# CPM_Uext.net
KiCad netlist of a schematic drawn in EAGLE
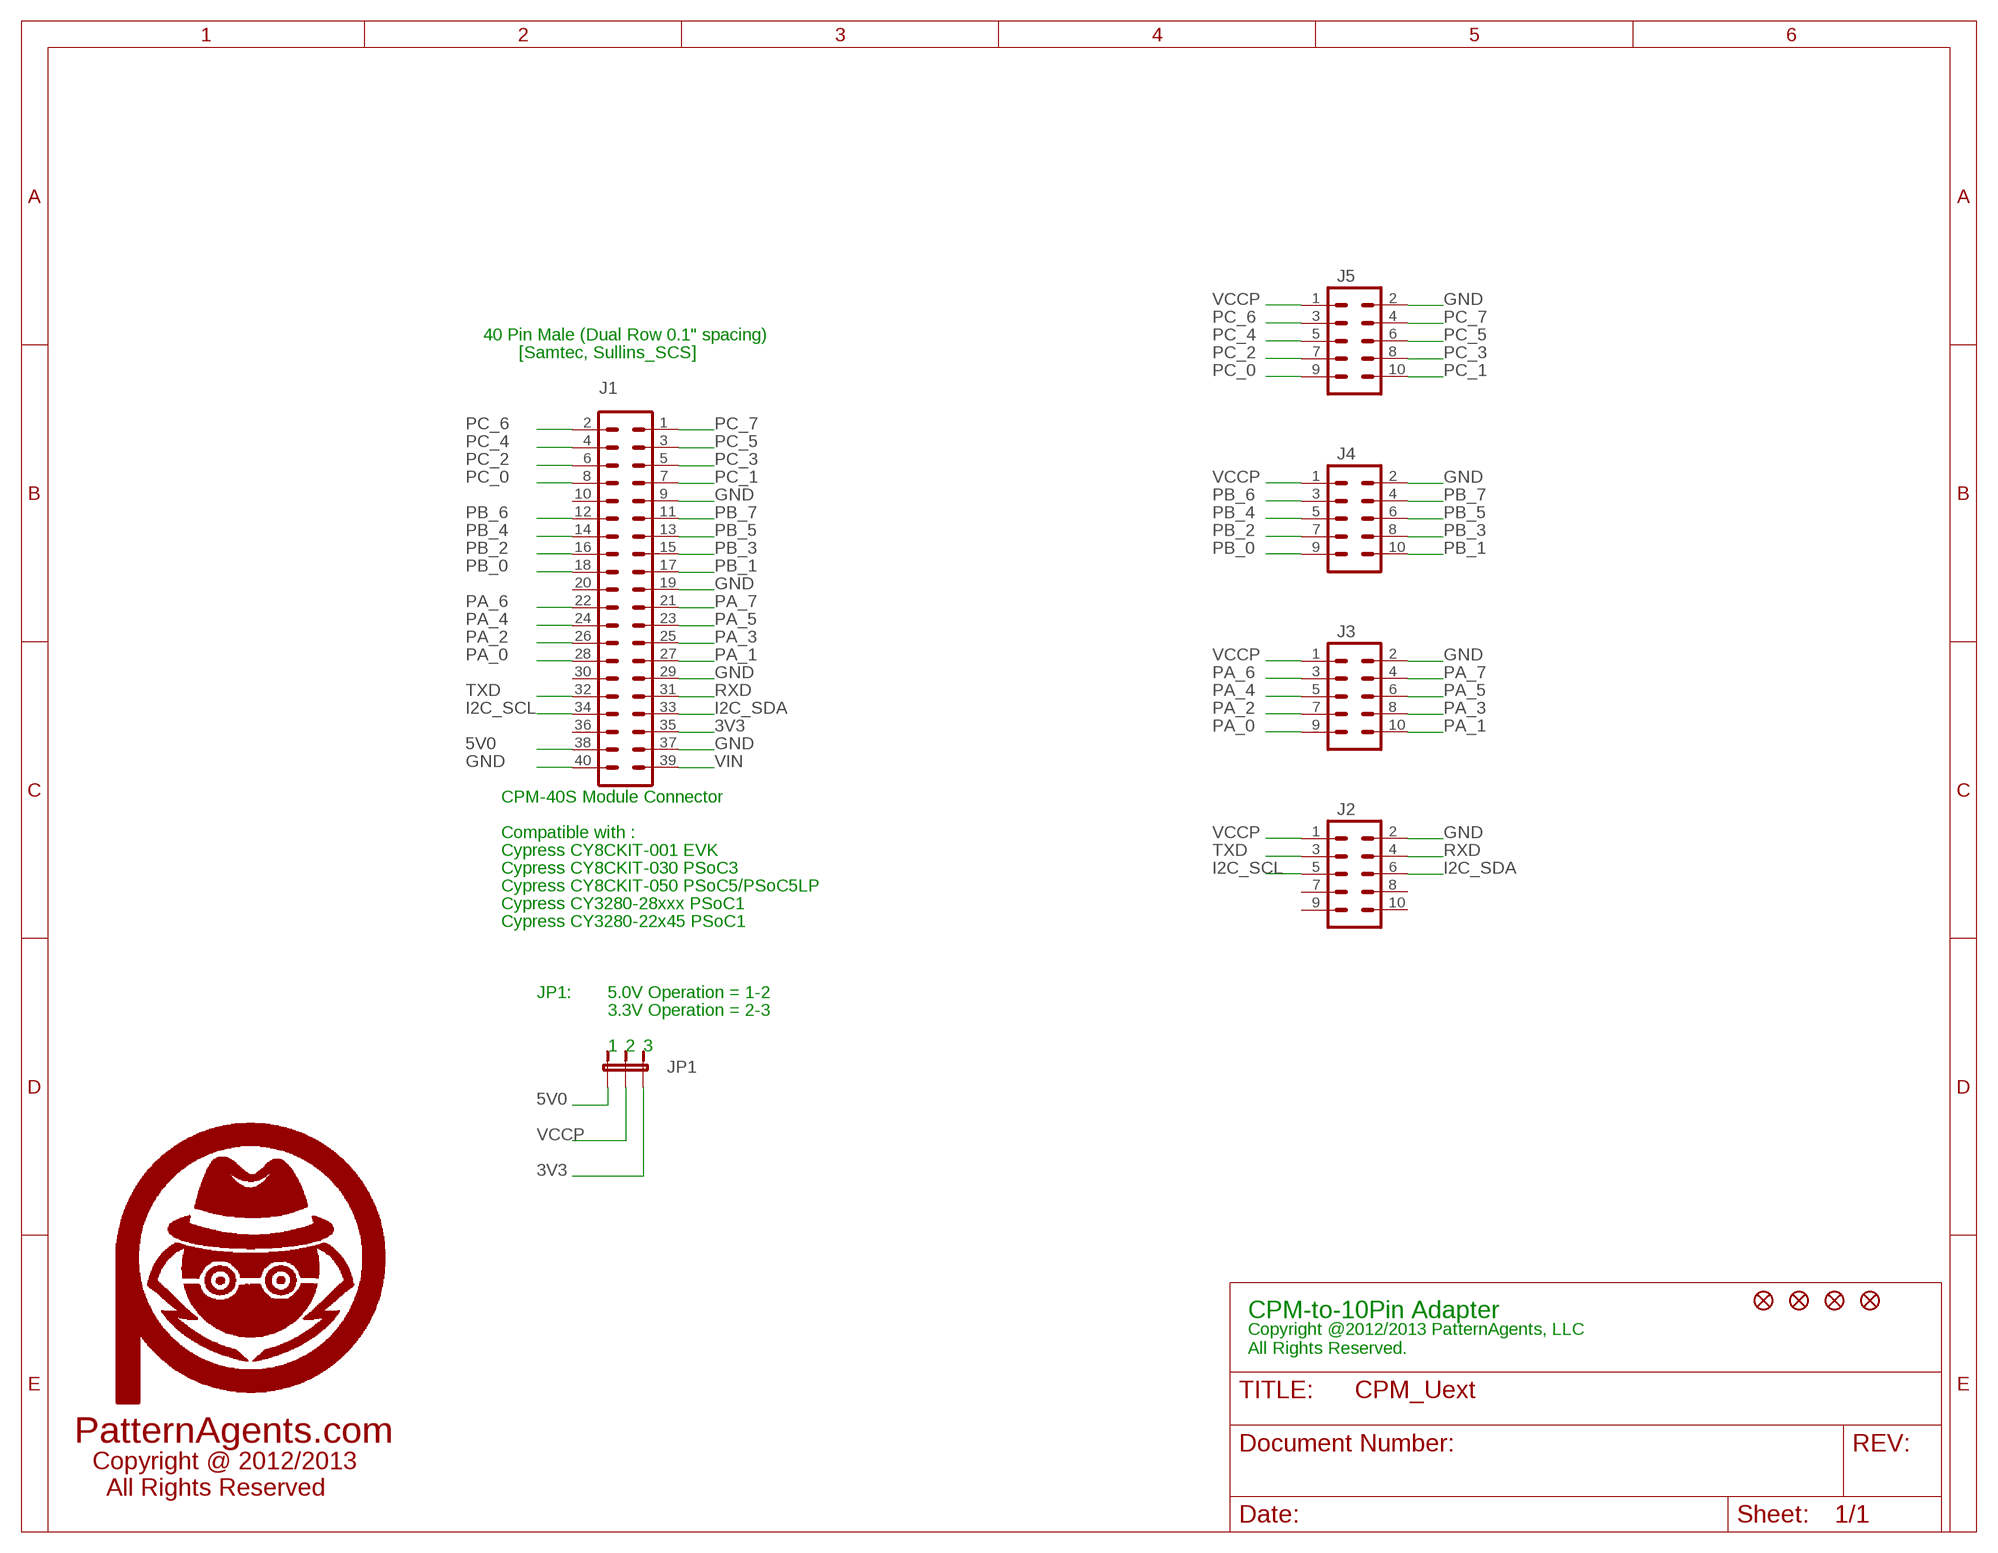
[diagram p0: schematic, sheet 1]

(export (version "E")
  (design (tool "Eeschema 10.0.6"))
  (components
    (comp (ref "J1")
      (value "SULLINS_SCS")
      (footprint "eagle-import:MA20-2")
      (fields (field (name "MF") "Sullins") (field (name "MPN") "PBC20DBAN"))
      (libsource (lib "eagle-import") (part "MA20-2"))
    )
    (comp (ref "J2")
      (value "M05X2")
      (footprint "eagle-import:2X5-UEXT")
      (libsource (lib "eagle-import") (part "M05X2"))
    )
    (comp (ref "J3")
      (value "M05X2")
      (footprint "eagle-import:2X5-UEXT")
      (libsource (lib "eagle-import") (part "M05X2"))
    )
    (comp (ref "J4")
      (value "M05X2")
      (footprint "eagle-import:2X5-UEXT")
      (libsource (lib "eagle-import") (part "M05X2"))
    )
    (comp (ref "J5")
      (value "M05X2")
      (footprint "eagle-import:2X5-UEXT")
      (libsource (lib "eagle-import") (part "M05X2"))
    )
    (comp (ref "JP1")
      (value "JUMPER-3PTH")
      (footprint "eagle-import:1X03")
      (libsource (lib "eagle-import") (part "JUMPER-3PTH"))
    )
    (comp (ref "JP2")
      (value "FIDUCIAL1.5X3")
      (footprint "eagle-import:FIDUCIAL-1.5X3")
      (libsource (lib "eagle-import") (part "FIDUCIAL1.5X3"))
    )
    (comp (ref "JP3")
      (value "FIDUCIAL1.5X3")
      (footprint "eagle-import:FIDUCIAL-1.5X3")
      (libsource (lib "eagle-import") (part "FIDUCIAL1.5X3"))
    )
    (comp (ref "JP4")
      (value "FIDUCIAL1.5X3")
      (footprint "eagle-import:FIDUCIAL-1.5X3")
      (libsource (lib "eagle-import") (part "FIDUCIAL1.5X3"))
    )
    (comp (ref "JP5")
      (value "FIDUCIAL1.5X3")
      (footprint "eagle-import:FIDUCIAL-1.5X3")
      (libsource (lib "eagle-import") (part "FIDUCIAL1.5X3"))
    )
    (comp (ref "U$1")
      (value "LOGO_PA_AGENTLARGE")
      (footprint "eagle-import:LOGO_PA_AGENT_LARGE")
      (libsource (lib "eagle-import") (part "LOGO_PA_AGENTLARGE"))
    )
  )
  (nets
    (net (code "1") (name "/3V3") (class "Default")
      (node (ref "J1") (pin "35") (pinfunction "35_35") (pintype "passive"))
      (node (ref "JP1") (pin "3") (pinfunction "3_3") (pintype "passive"))
    )
    (net (code "2") (name "/5V0") (class "Default")
      (node (ref "J1") (pin "38") (pinfunction "38_38") (pintype "passive"))
      (node (ref "JP1") (pin "1") (pinfunction "1_1") (pintype "passive"))
    )
    (net (code "3") (name "/GND") (class "Default")
      (node (ref "J1") (pin "19") (pinfunction "19_19") (pintype "passive"))
      (node (ref "J1") (pin "29") (pinfunction "29_29") (pintype "passive"))
      (node (ref "J1") (pin "37") (pinfunction "37_37") (pintype "passive"))
      (node (ref "J1") (pin "40") (pinfunction "40_40") (pintype "passive"))
      (node (ref "J1") (pin "9") (pinfunction "9_9") (pintype "passive"))
      (node (ref "J2") (pin "2") (pinfunction "2_2") (pintype "passive"))
      (node (ref "J3") (pin "2") (pinfunction "2_2") (pintype "passive"))
      (node (ref "J4") (pin "2") (pinfunction "2_2") (pintype "passive"))
      (node (ref "J5") (pin "2") (pinfunction "2_2") (pintype "passive"))
    )
    (net (code "4") (name "/I2C_SCL") (class "Default")
      (node (ref "J1") (pin "34") (pinfunction "34_34") (pintype "passive"))
      (node (ref "J2") (pin "5") (pinfunction "5_5") (pintype "passive"))
    )
    (net (code "5") (name "/I2C_SDA") (class "Default")
      (node (ref "J1") (pin "33") (pinfunction "33_33") (pintype "passive"))
      (node (ref "J2") (pin "6") (pinfunction "6_6") (pintype "passive"))
    )
    (net (code "6") (name "/PA_0") (class "Default")
      (node (ref "J1") (pin "28") (pinfunction "28_28") (pintype "passive"))
      (node (ref "J3") (pin "9") (pinfunction "9_9") (pintype "passive"))
    )
    (net (code "7") (name "/PA_1") (class "Default")
      (node (ref "J1") (pin "27") (pinfunction "27_27") (pintype "passive"))
      (node (ref "J3") (pin "10") (pinfunction "10_10") (pintype "passive"))
    )
    (net (code "8") (name "/PA_2") (class "Default")
      (node (ref "J1") (pin "26") (pinfunction "26_26") (pintype "passive"))
      (node (ref "J3") (pin "7") (pinfunction "7_7") (pintype "passive"))
    )
    (net (code "9") (name "/PA_3") (class "Default")
      (node (ref "J1") (pin "25") (pinfunction "25_25") (pintype "passive"))
      (node (ref "J3") (pin "8") (pinfunction "8_8") (pintype "passive"))
    )
    (net (code "10") (name "/PA_4") (class "Default")
      (node (ref "J1") (pin "24") (pinfunction "24_24") (pintype "passive"))
      (node (ref "J3") (pin "5") (pinfunction "5_5") (pintype "passive"))
    )
    (net (code "11") (name "/PA_5") (class "Default")
      (node (ref "J1") (pin "23") (pinfunction "23_23") (pintype "passive"))
      (node (ref "J3") (pin "6") (pinfunction "6_6") (pintype "passive"))
    )
    (net (code "12") (name "/PA_6") (class "Default")
      (node (ref "J1") (pin "22") (pinfunction "22_22") (pintype "passive"))
      (node (ref "J3") (pin "3") (pinfunction "3_3") (pintype "passive"))
    )
    (net (code "13") (name "/PA_7") (class "Default")
      (node (ref "J1") (pin "21") (pinfunction "21_21") (pintype "passive"))
      (node (ref "J3") (pin "4") (pinfunction "4_4") (pintype "passive"))
    )
    (net (code "14") (name "/PB_0") (class "Default")
      (node (ref "J1") (pin "18") (pinfunction "18_18") (pintype "passive"))
      (node (ref "J4") (pin "9") (pinfunction "9_9") (pintype "passive"))
    )
    (net (code "15") (name "/PB_1") (class "Default")
      (node (ref "J1") (pin "17") (pinfunction "17_17") (pintype "passive"))
      (node (ref "J4") (pin "10") (pinfunction "10_10") (pintype "passive"))
    )
    (net (code "16") (name "/PB_2") (class "Default")
      (node (ref "J1") (pin "16") (pinfunction "16_16") (pintype "passive"))
      (node (ref "J4") (pin "7") (pinfunction "7_7") (pintype "passive"))
    )
    (net (code "17") (name "/PB_3") (class "Default")
      (node (ref "J1") (pin "15") (pinfunction "15_15") (pintype "passive"))
      (node (ref "J4") (pin "8") (pinfunction "8_8") (pintype "passive"))
    )
    (net (code "18") (name "/PB_4") (class "Default")
      (node (ref "J1") (pin "14") (pinfunction "14_14") (pintype "passive"))
      (node (ref "J4") (pin "5") (pinfunction "5_5") (pintype "passive"))
    )
    (net (code "19") (name "/PB_5") (class "Default")
      (node (ref "J1") (pin "13") (pinfunction "13_13") (pintype "passive"))
      (node (ref "J4") (pin "6") (pinfunction "6_6") (pintype "passive"))
    )
    (net (code "20") (name "/PB_6") (class "Default")
      (node (ref "J1") (pin "12") (pinfunction "12_12") (pintype "passive"))
      (node (ref "J4") (pin "3") (pinfunction "3_3") (pintype "passive"))
    )
    (net (code "21") (name "/PB_7") (class "Default")
      (node (ref "J1") (pin "11") (pinfunction "11_11") (pintype "passive"))
      (node (ref "J4") (pin "4") (pinfunction "4_4") (pintype "passive"))
    )
    (net (code "22") (name "/PC_0") (class "Default")
      (node (ref "J1") (pin "8") (pinfunction "8_8") (pintype "passive"))
      (node (ref "J5") (pin "9") (pinfunction "9_9") (pintype "passive"))
    )
    (net (code "23") (name "/PC_1") (class "Default")
      (node (ref "J1") (pin "7") (pinfunction "7_7") (pintype "passive"))
      (node (ref "J5") (pin "10") (pinfunction "10_10") (pintype "passive"))
    )
    (net (code "24") (name "/PC_2") (class "Default")
      (node (ref "J1") (pin "6") (pinfunction "6_6") (pintype "passive"))
      (node (ref "J5") (pin "7") (pinfunction "7_7") (pintype "passive"))
    )
    (net (code "25") (name "/PC_3") (class "Default")
      (node (ref "J1") (pin "5") (pinfunction "5_5") (pintype "passive"))
      (node (ref "J5") (pin "8") (pinfunction "8_8") (pintype "passive"))
    )
    (net (code "26") (name "/PC_4") (class "Default")
      (node (ref "J1") (pin "4") (pinfunction "4_4") (pintype "passive"))
      (node (ref "J5") (pin "5") (pinfunction "5_5") (pintype "passive"))
    )
    (net (code "27") (name "/PC_5") (class "Default")
      (node (ref "J1") (pin "3") (pinfunction "3_3") (pintype "passive"))
      (node (ref "J5") (pin "6") (pinfunction "6_6") (pintype "passive"))
    )
    (net (code "28") (name "/PC_6") (class "Default")
      (node (ref "J1") (pin "2") (pinfunction "2_2") (pintype "passive"))
      (node (ref "J5") (pin "3") (pinfunction "3_3") (pintype "passive"))
    )
    (net (code "29") (name "/PC_7") (class "Default")
      (node (ref "J1") (pin "1") (pinfunction "1_1") (pintype "passive"))
      (node (ref "J5") (pin "4") (pinfunction "4_4") (pintype "passive"))
    )
    (net (code "30") (name "/RXD") (class "Default")
      (node (ref "J1") (pin "31") (pinfunction "31_31") (pintype "passive"))
      (node (ref "J2") (pin "4") (pinfunction "4_4") (pintype "passive"))
    )
    (net (code "31") (name "/TXD") (class "Default")
      (node (ref "J1") (pin "32") (pinfunction "32_32") (pintype "passive"))
      (node (ref "J2") (pin "3") (pinfunction "3_3") (pintype "passive"))
    )
    (net (code "32") (name "/VCCP") (class "Default")
      (node (ref "J2") (pin "1") (pinfunction "1_1") (pintype "passive"))
      (node (ref "J3") (pin "1") (pinfunction "1_1") (pintype "passive"))
      (node (ref "J4") (pin "1") (pinfunction "1_1") (pintype "passive"))
      (node (ref "J5") (pin "1") (pinfunction "1_1") (pintype "passive"))
      (node (ref "JP1") (pin "2") (pinfunction "2_2") (pintype "passive"))
    )
    (net (code "33") (name "/VIN") (class "Default")
      (node (ref "J1") (pin "39") (pinfunction "39_39") (pintype "passive"))
    )
    (net (code "34") (name "unconnected-(J1-Pad10)") (class "Default")
      (node (ref "J1") (pin "10") (pinfunction "10_10") (pintype "passive"))
    )
    (net (code "35") (name "unconnected-(J1-Pad20)") (class "Default")
      (node (ref "J1") (pin "20") (pinfunction "20_20") (pintype "passive"))
    )
    (net (code "36") (name "unconnected-(J1-Pad30)") (class "Default")
      (node (ref "J1") (pin "30") (pinfunction "30_30") (pintype "passive"))
    )
    (net (code "37") (name "unconnected-(J1-Pad36)") (class "Default")
      (node (ref "J1") (pin "36") (pinfunction "36_36") (pintype "passive"))
    )
    (net (code "38") (name "unconnected-(J2-Pad7)") (class "Default")
      (node (ref "J2") (pin "7") (pinfunction "7_7") (pintype "passive"))
    )
    (net (code "39") (name "unconnected-(J2-Pad8)") (class "Default")
      (node (ref "J2") (pin "8") (pinfunction "8_8") (pintype "passive"))
    )
    (net (code "40") (name "unconnected-(J2-Pad9)") (class "Default")
      (node (ref "J2") (pin "9") (pinfunction "9_9") (pintype "passive"))
    )
    (net (code "41") (name "unconnected-(J2-Pad10)") (class "Default")
      (node (ref "J2") (pin "10") (pinfunction "10_10") (pintype "passive"))
    )
  )
)
